# TDBR_MCP9802.net
KiCad netlist of a schematic drawn in EAGLE
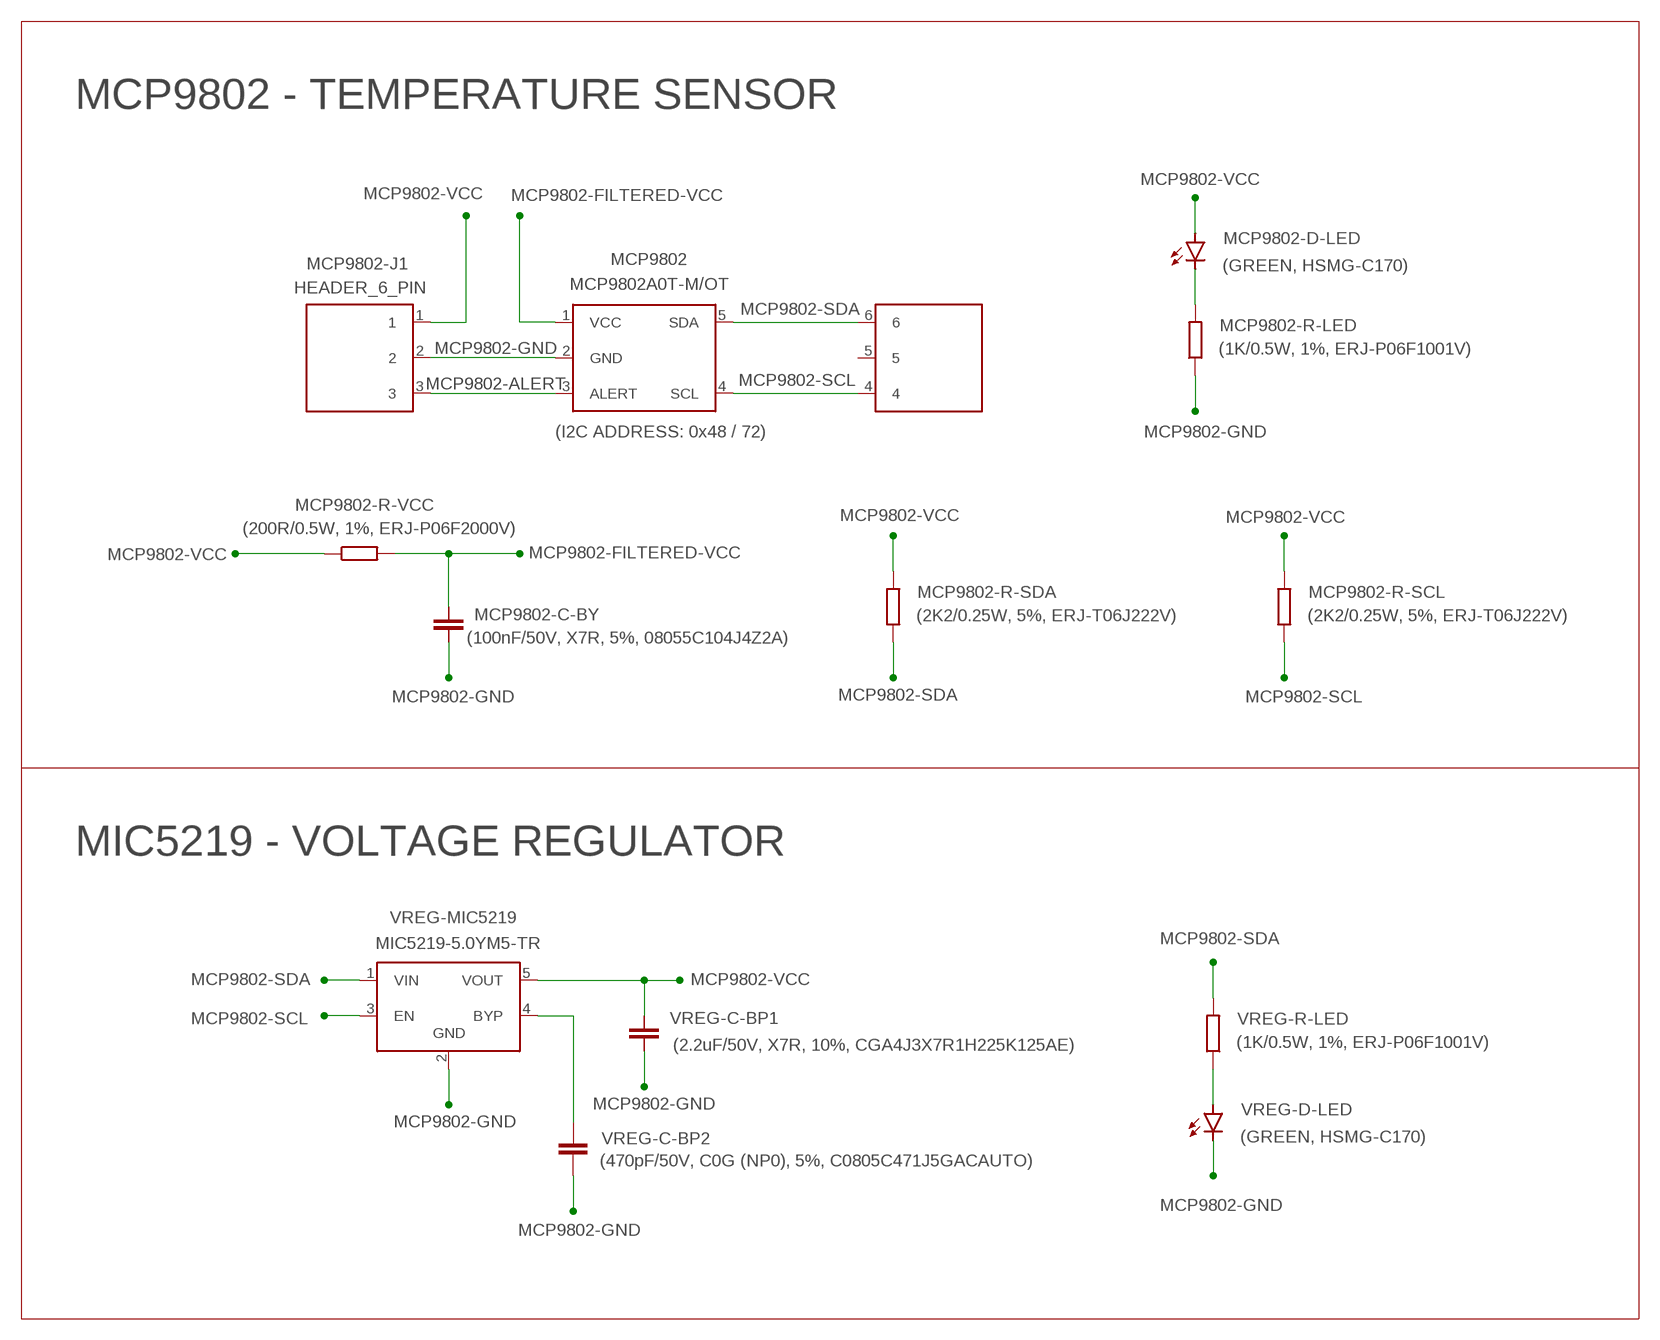
[diagram p0: schematic, sheet 1]

(export (version "E")
  (design (tool "Eeschema 10.0.6"))
  (components
    (comp (ref "MCP9802")
      (value "MCP9802A0T-M/OT")
      (footprint "eagle-import:SOT-23-5")
      (libsource (lib "eagle-import") (part "MCP9802A0T-M/OT"))
    )
    (comp (ref "MCP9802-C-BY")
      (value "(100nF/50V, X7R, 5%, 08055C104J4Z2A)")
      (footprint "eagle-import:0805")
      (libsource (lib "eagle-import") (part "08055C104J4Z2A"))
    )
    (comp (ref "MCP9802-D-LED")
      (value "(GREEN, HSMG-C170)")
      (footprint "eagle-import:DIODE_0805")
      (libsource (lib "eagle-import") (part "HSMG-C170"))
    )
    (comp (ref "MCP9802-J1")
      (value "HEADER_6_PIN")
      (footprint "eagle-import:HEADER_2.54MM_6_PIN_VER")
      (libsource (lib "eagle-import") (part "HEADER_6_PIN"))
    )
    (comp (ref "MCP9802-R-LED")
      (value "(1K/0.5W, 1%, ERJ-P06F1001V)")
      (footprint "eagle-import:0805")
      (libsource (lib "eagle-import") (part "ERJ-P06F1001V"))
    )
    (comp (ref "MCP9802-R-SCL")
      (value "(2K2/0.25W, 5%, ERJ-T06J222V)")
      (footprint "eagle-import:0805")
      (libsource (lib "eagle-import") (part "ERJ-T06J222V"))
    )
    (comp (ref "MCP9802-R-SDA")
      (value "(2K2/0.25W, 5%, ERJ-T06J222V)")
      (footprint "eagle-import:0805")
      (libsource (lib "eagle-import") (part "ERJ-T06J222V"))
    )
    (comp (ref "MCP9802-R-VCC")
      (value "(200R/0.5W, 1%, ERJ-P06F2000V)")
      (footprint "eagle-import:0805")
      (libsource (lib "eagle-import") (part "ERJ-P06F2000V"))
    )
    (comp (ref "VREG-C-BP1")
      (value "(2.2uF/50V, X7R, 10%, CGA4J3X7R1H225K125AE)")
      (footprint "eagle-import:0805")
      (libsource (lib "eagle-import") (part "CGA4J3X7R1H225K125AE"))
    )
    (comp (ref "VREG-C-BP2")
      (value "(470pF/50V, C0G (NP0), 5%, C0805C471J5GACAUTO)")
      (footprint "eagle-import:0805")
      (libsource (lib "eagle-import") (part "C0805X471J5GACTU"))
    )
    (comp (ref "VREG-D-LED")
      (value "(GREEN, HSMG-C170)")
      (footprint "eagle-import:DIODE_0805")
      (libsource (lib "eagle-import") (part "HSMG-C170"))
    )
    (comp (ref "VREG-MIC5219")
      (value "MIC5219-5.0YM5-TR")
      (footprint "eagle-import:SOT-23-5")
      (libsource (lib "eagle-import") (part "MIC5219-5.0YM5-TR"))
    )
    (comp (ref "VREG-R-LED")
      (value "(1K/0.5W, 1%, ERJ-P06F1001V)")
      (footprint "eagle-import:0805")
      (libsource (lib "eagle-import") (part "ERJ-P06F1001V"))
    )
  )
  (nets
    (net (code "1") (name "/MCP9802-ALERT") (class "Default")
      (node (ref "MCP9802") (pin "3") (pinfunction "ALERT_3") (pintype "bidirectional"))
      (node (ref "MCP9802-J1") (pin "3") (pinfunction "3_3") (pintype "bidirectional"))
    )
    (net (code "2") (name "/MCP9802-FILTERED-VCC") (class "Default")
      (node (ref "MCP9802") (pin "1") (pinfunction "VCC_1") (pintype "power_in"))
      (node (ref "MCP9802-C-BY") (pin "1") (pinfunction "A_1") (pintype "passive"))
      (node (ref "MCP9802-R-VCC") (pin "2") (pinfunction "2_2") (pintype "passive"))
    )
    (net (code "3") (name "/MCP9802-GND") (class "Default")
      (node (ref "MCP9802") (pin "2") (pinfunction "GND_2") (pintype "power_in"))
      (node (ref "MCP9802-C-BY") (pin "2") (pinfunction "C_2") (pintype "passive"))
      (node (ref "MCP9802-J1") (pin "2") (pinfunction "2_2") (pintype "bidirectional"))
      (node (ref "MCP9802-R-LED") (pin "1") (pinfunction "1_1") (pintype "passive"))
      (node (ref "VREG-C-BP1") (pin "1") (pinfunction "A_1") (pintype "passive"))
      (node (ref "VREG-C-BP2") (pin "1") (pinfunction "1_1") (pintype "passive"))
      (node (ref "VREG-D-LED") (pin "C") (pinfunction "C_C") (pintype "passive"))
      (node (ref "VREG-MIC5219") (pin "2") (pinfunction "GND_2") (pintype "power_in"))
    )
    (net (code "4") (name "/MCP9802-SCL") (class "Default")
      (node (ref "MCP9802") (pin "4") (pinfunction "SCL_4") (pintype "bidirectional"))
      (node (ref "MCP9802-J1") (pin "4") (pinfunction "4_4") (pintype "bidirectional"))
      (node (ref "MCP9802-R-SCL") (pin "1") (pinfunction "1_1") (pintype "passive"))
      (node (ref "VREG-MIC5219") (pin "3") (pinfunction "EN_3") (pintype "passive"))
    )
    (net (code "5") (name "/MCP9802-SDA") (class "Default")
      (node (ref "MCP9802") (pin "5") (pinfunction "SDA_5") (pintype "bidirectional"))
      (node (ref "MCP9802-J1") (pin "6") (pinfunction "6_6") (pintype "bidirectional"))
      (node (ref "MCP9802-R-SDA") (pin "1") (pinfunction "1_1") (pintype "passive"))
      (node (ref "VREG-MIC5219") (pin "1") (pinfunction "VIN_1") (pintype "passive"))
      (node (ref "VREG-R-LED") (pin "2") (pinfunction "2_2") (pintype "passive"))
    )
    (net (code "6") (name "/MCP9802-VCC") (class "Default")
      (node (ref "MCP9802-D-LED") (pin "A") (pinfunction "A_A") (pintype "passive"))
      (node (ref "MCP9802-J1") (pin "1") (pinfunction "1_1") (pintype "bidirectional"))
      (node (ref "MCP9802-R-SCL") (pin "2") (pinfunction "2_2") (pintype "passive"))
      (node (ref "MCP9802-R-SDA") (pin "2") (pinfunction "2_2") (pintype "passive"))
      (node (ref "MCP9802-R-VCC") (pin "1") (pinfunction "1_1") (pintype "passive"))
      (node (ref "VREG-C-BP1") (pin "2") (pinfunction "C_2") (pintype "passive"))
      (node (ref "VREG-MIC5219") (pin "5") (pinfunction "VOUT_5") (pintype "passive"))
    )
    (net (code "7") (name "Net-(MCP9802-D-LED-PadC)") (class "Default")
      (node (ref "MCP9802-D-LED") (pin "C") (pinfunction "C_C") (pintype "passive"))
      (node (ref "MCP9802-R-LED") (pin "2") (pinfunction "2_2") (pintype "passive"))
    )
    (net (code "8") (name "Net-(VREG-D-LED-PadA)") (class "Default")
      (node (ref "VREG-D-LED") (pin "A") (pinfunction "A_A") (pintype "passive"))
      (node (ref "VREG-R-LED") (pin "1") (pinfunction "1_1") (pintype "passive"))
    )
    (net (code "9") (name "Net-(VREG-MIC5219-BYP)") (class "Default")
      (node (ref "VREG-C-BP2") (pin "2") (pinfunction "2_2") (pintype "passive"))
      (node (ref "VREG-MIC5219") (pin "4") (pinfunction "BYP_4") (pintype "passive"))
    )
    (net (code "10") (name "unconnected-(MCP9802-J1-Pad5)") (class "Default")
      (node (ref "MCP9802-J1") (pin "5") (pinfunction "5_5") (pintype "bidirectional"))
    )
  )
)
